# Pressure_nopins.net
KiCad netlist of a schematic drawn in EAGLE
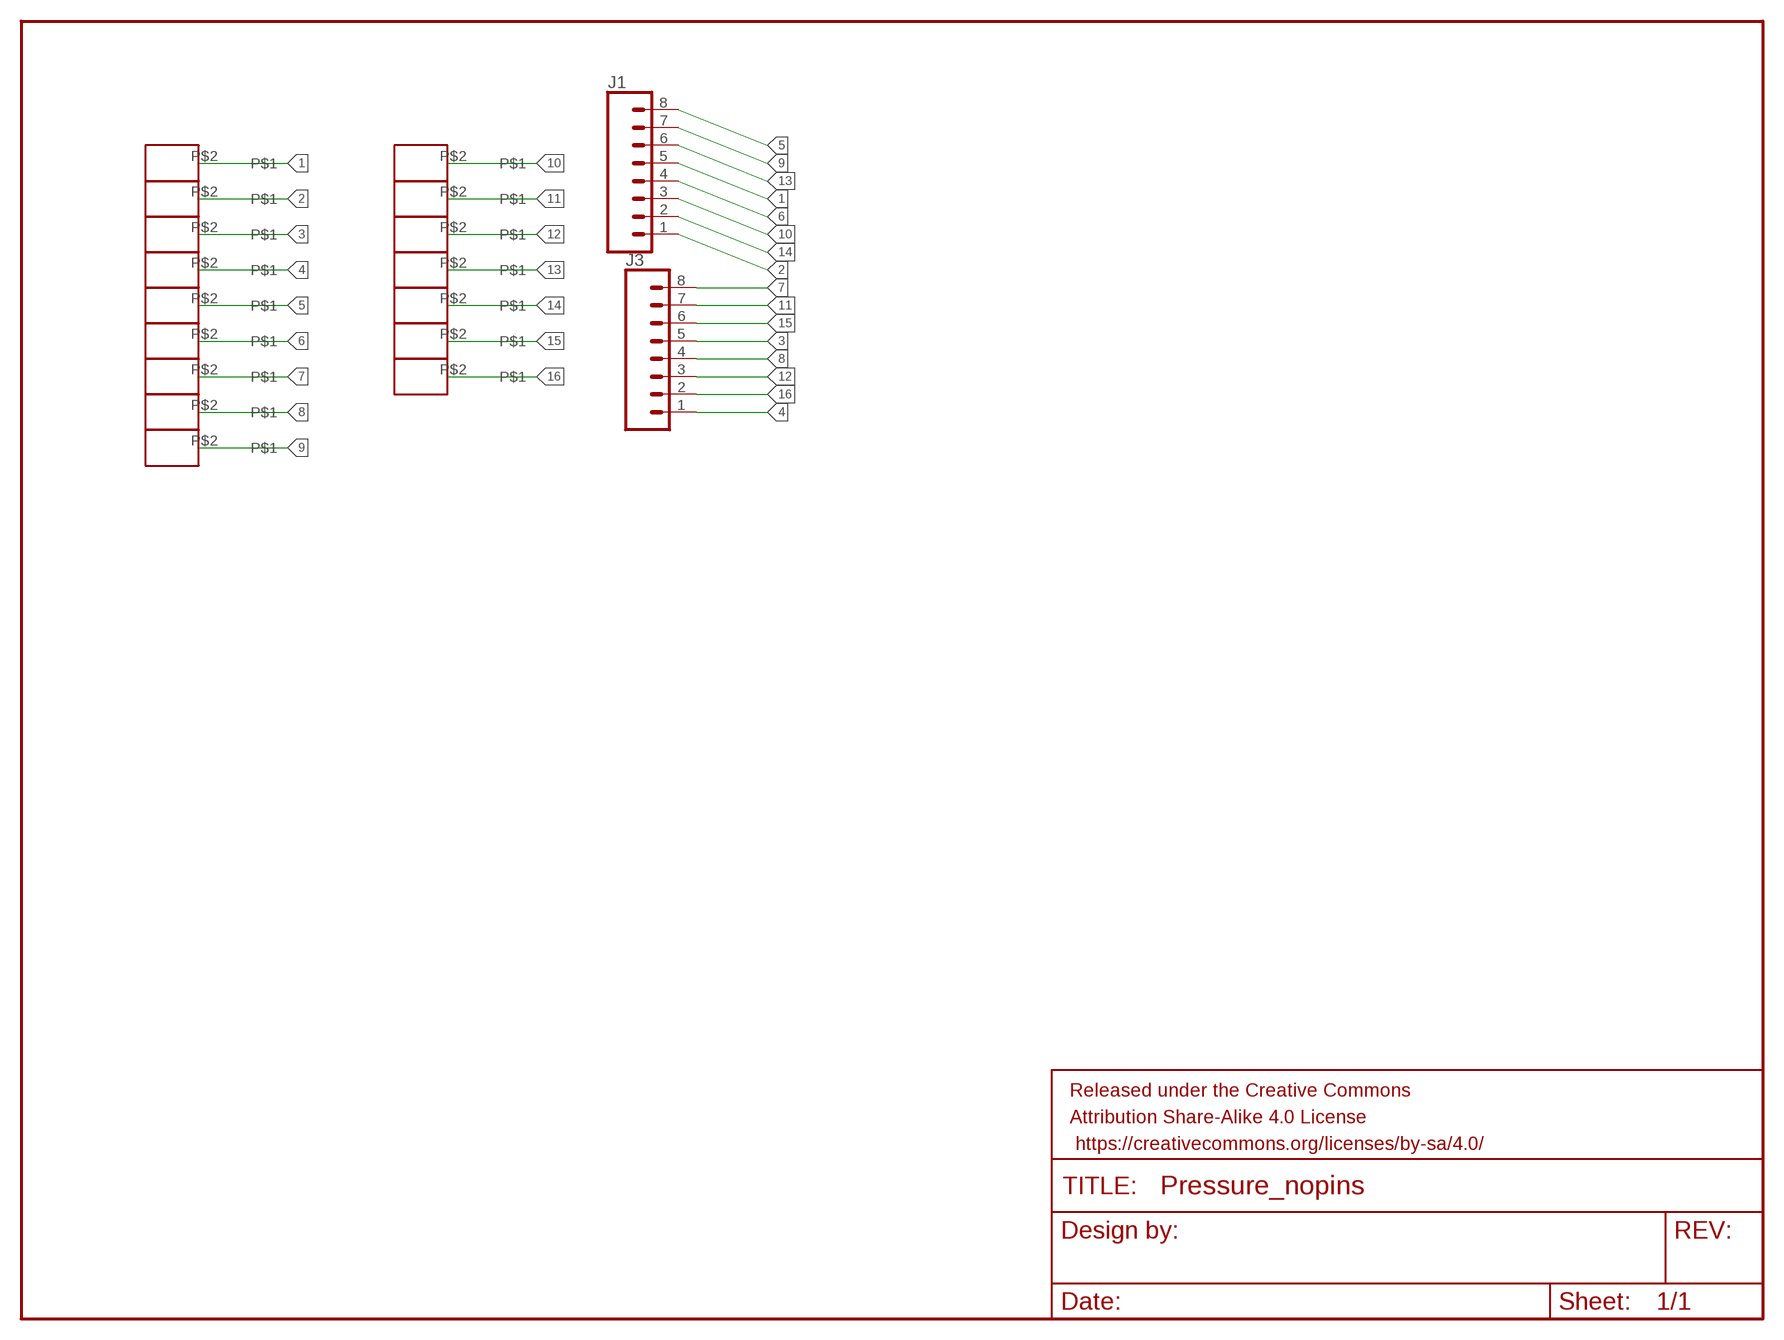
[diagram p0: schematic, sheet 1]

(export (version "E")
  (design (tool "Eeschema 10.0.6"))
  (components
    (comp (ref "FRAME1")
      (value "FRAME-LETTERNO_PACKAGE")
      (footprint "eagle-import:DUMMY")
      (fields (field (name "DESIGNER") "Nobody"))
      (libsource (lib "eagle-import") (part "FRAME-LETTERNO_PACKAGE"))
    )
    (comp (ref "J1")
      (value "CONN_08SMD-MALE")
      (footprint "eagle-import:1X08_SMD_MALE")
      (libsource (lib "eagle-import") (part "CONN_08SMD-MALE"))
    )
    (comp (ref "J3")
      (value "CONN_08SMD-MALE")
      (footprint "eagle-import:1X08_SMD_MALE")
      (libsource (lib "eagle-import") (part "CONN_08SMD-MALE"))
    )
    (comp (ref "U$1")
      (value "250MIL_1X1")
      (footprint "eagle-import:250MIL_1X1")
      (libsource (lib "eagle-import") (part "250MIL_1X1"))
    )
    (comp (ref "U$2")
      (value "250MIL_1X1")
      (footprint "eagle-import:250MIL_1X1")
      (libsource (lib "eagle-import") (part "250MIL_1X1"))
    )
    (comp (ref "U$3")
      (value "250MIL_1X1")
      (footprint "eagle-import:250MIL_1X1")
      (libsource (lib "eagle-import") (part "250MIL_1X1"))
    )
    (comp (ref "U$4")
      (value "250MIL_1X1")
      (footprint "eagle-import:250MIL_1X1")
      (libsource (lib "eagle-import") (part "250MIL_1X1"))
    )
    (comp (ref "U$5")
      (value "250MIL_1X1")
      (footprint "eagle-import:250MIL_1X1")
      (libsource (lib "eagle-import") (part "250MIL_1X1"))
    )
    (comp (ref "U$6")
      (value "250MIL_1X1")
      (footprint "eagle-import:250MIL_1X1")
      (libsource (lib "eagle-import") (part "250MIL_1X1"))
    )
    (comp (ref "U$7")
      (value "250MIL_1X1")
      (footprint "eagle-import:250MIL_1X1")
      (libsource (lib "eagle-import") (part "250MIL_1X1"))
    )
    (comp (ref "U$8")
      (value "250MIL_1X1")
      (footprint "eagle-import:250MIL_1X1")
      (libsource (lib "eagle-import") (part "250MIL_1X1"))
    )
    (comp (ref "U$9")
      (value "250MIL_1X1")
      (footprint "eagle-import:250MIL_1X1")
      (libsource (lib "eagle-import") (part "250MIL_1X1"))
    )
    (comp (ref "U$10")
      (value "250MIL_1X1")
      (footprint "eagle-import:250MIL_1X1")
      (libsource (lib "eagle-import") (part "250MIL_1X1"))
    )
    (comp (ref "U$11")
      (value "250MIL_1X1")
      (footprint "eagle-import:250MIL_1X1")
      (libsource (lib "eagle-import") (part "250MIL_1X1"))
    )
    (comp (ref "U$12")
      (value "250MIL_1X1")
      (footprint "eagle-import:250MIL_1X1")
      (libsource (lib "eagle-import") (part "250MIL_1X1"))
    )
    (comp (ref "U$13")
      (value "250MIL_1X1")
      (footprint "eagle-import:250MIL_1X1")
      (libsource (lib "eagle-import") (part "250MIL_1X1"))
    )
    (comp (ref "U$14")
      (value "250MIL_1X1")
      (footprint "eagle-import:250MIL_1X1")
      (libsource (lib "eagle-import") (part "250MIL_1X1"))
    )
    (comp (ref "U$15")
      (value "250MIL_1X1")
      (footprint "eagle-import:250MIL_1X1")
      (libsource (lib "eagle-import") (part "250MIL_1X1"))
    )
    (comp (ref "U$16")
      (value "250MIL_1X1")
      (footprint "eagle-import:250MIL_1X1")
      (libsource (lib "eagle-import") (part "250MIL_1X1"))
    )
  )
  (nets
    (net (code "1") (name "1") (class "Default")
      (node (ref "J1") (pin "5") (pinfunction "5_5") (pintype "passive"))
      (node (ref "U$1") (pin "P$2") (pinfunction "P$1_P$2") (pintype "bidirectional"))
    )
    (net (code "2") (name "2") (class "Default")
      (node (ref "J1") (pin "1") (pinfunction "1_1") (pintype "passive"))
      (node (ref "U$2") (pin "P$2") (pinfunction "P$1_P$2") (pintype "bidirectional"))
    )
    (net (code "3") (name "3") (class "Default")
      (node (ref "J3") (pin "5") (pinfunction "5_5") (pintype "passive"))
      (node (ref "U$3") (pin "P$2") (pinfunction "P$1_P$2") (pintype "bidirectional"))
    )
    (net (code "4") (name "4") (class "Default")
      (node (ref "J3") (pin "1") (pinfunction "1_1") (pintype "passive"))
      (node (ref "U$4") (pin "P$2") (pinfunction "P$1_P$2") (pintype "bidirectional"))
    )
    (net (code "5") (name "5") (class "Default")
      (node (ref "J1") (pin "8") (pinfunction "8_8") (pintype "passive"))
      (node (ref "U$5") (pin "P$2") (pinfunction "P$1_P$2") (pintype "bidirectional"))
    )
    (net (code "6") (name "6") (class "Default")
      (node (ref "J1") (pin "4") (pinfunction "4_4") (pintype "passive"))
      (node (ref "U$6") (pin "P$2") (pinfunction "P$1_P$2") (pintype "bidirectional"))
    )
    (net (code "7") (name "7") (class "Default")
      (node (ref "J3") (pin "8") (pinfunction "8_8") (pintype "passive"))
      (node (ref "U$7") (pin "P$2") (pinfunction "P$1_P$2") (pintype "bidirectional"))
    )
    (net (code "8") (name "8") (class "Default")
      (node (ref "J3") (pin "4") (pinfunction "4_4") (pintype "passive"))
      (node (ref "U$8") (pin "P$2") (pinfunction "P$1_P$2") (pintype "bidirectional"))
    )
    (net (code "9") (name "9") (class "Default")
      (node (ref "J1") (pin "7") (pinfunction "7_7") (pintype "passive"))
      (node (ref "U$9") (pin "P$2") (pinfunction "P$1_P$2") (pintype "bidirectional"))
    )
    (net (code "10") (name "10") (class "Default")
      (node (ref "J1") (pin "3") (pinfunction "3_3") (pintype "passive"))
      (node (ref "U$10") (pin "P$2") (pinfunction "P$1_P$2") (pintype "bidirectional"))
    )
    (net (code "11") (name "11") (class "Default")
      (node (ref "J3") (pin "7") (pinfunction "7_7") (pintype "passive"))
      (node (ref "U$11") (pin "P$2") (pinfunction "P$1_P$2") (pintype "bidirectional"))
    )
    (net (code "12") (name "12") (class "Default")
      (node (ref "J3") (pin "3") (pinfunction "3_3") (pintype "passive"))
      (node (ref "U$12") (pin "P$2") (pinfunction "P$1_P$2") (pintype "bidirectional"))
    )
    (net (code "13") (name "13") (class "Default")
      (node (ref "J1") (pin "6") (pinfunction "6_6") (pintype "passive"))
      (node (ref "U$13") (pin "P$2") (pinfunction "P$1_P$2") (pintype "bidirectional"))
    )
    (net (code "14") (name "14") (class "Default")
      (node (ref "J1") (pin "2") (pinfunction "2_2") (pintype "passive"))
      (node (ref "U$14") (pin "P$2") (pinfunction "P$1_P$2") (pintype "bidirectional"))
    )
    (net (code "15") (name "15") (class "Default")
      (node (ref "J3") (pin "6") (pinfunction "6_6") (pintype "passive"))
      (node (ref "U$15") (pin "P$2") (pinfunction "P$1_P$2") (pintype "bidirectional"))
    )
    (net (code "16") (name "16") (class "Default")
      (node (ref "J3") (pin "2") (pinfunction "2_2") (pintype "passive"))
      (node (ref "U$16") (pin "P$2") (pinfunction "P$1_P$2") (pintype "bidirectional"))
    )
  )
)
